# DetectLabel_Simple.net
KiCad netlist of a schematic drawn in EAGLE
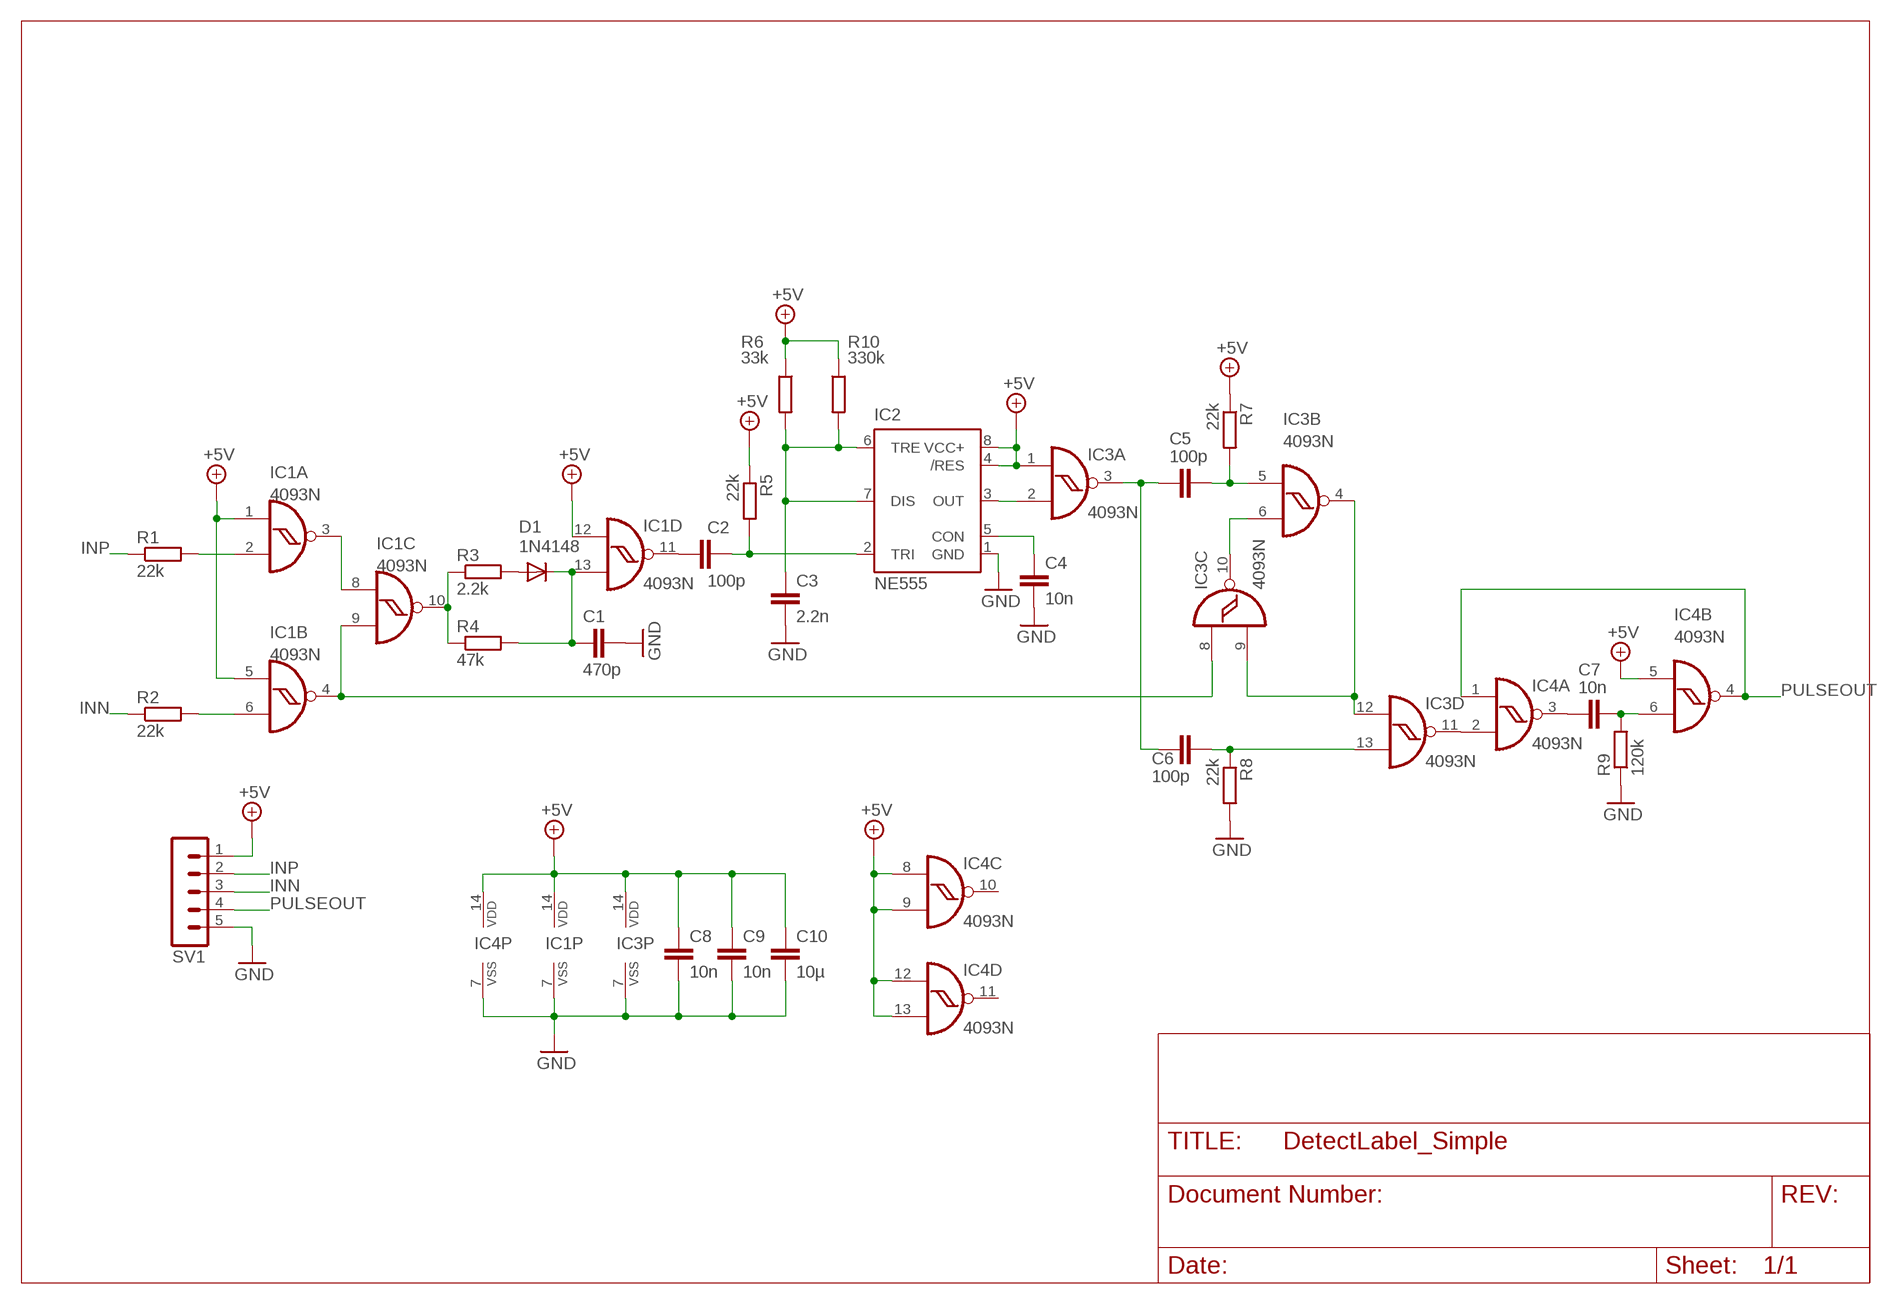
[diagram p0: schematic, sheet 1]

(export (version "E")
  (design (tool "Eeschema 10.0.6"))
  (components
    (comp (ref "C1")
      (value "470p")
      (footprint "eagle-import:C050-025X075")
      (libsource (lib "eagle-import") (part "C-EU050-025X075"))
    )
    (comp (ref "C2")
      (value "100p")
      (footprint "eagle-import:C050-025X075")
      (libsource (lib "eagle-import") (part "C-EU050-025X075"))
    )
    (comp (ref "C3")
      (value "2.2n")
      (footprint "eagle-import:C050-025X075")
      (libsource (lib "eagle-import") (part "C-EU050-025X075"))
    )
    (comp (ref "C4")
      (value "10n")
      (footprint "eagle-import:C050-025X075")
      (libsource (lib "eagle-import") (part "C-EU050-025X075"))
    )
    (comp (ref "C5")
      (value "100p")
      (footprint "eagle-import:C050-025X075")
      (libsource (lib "eagle-import") (part "C-EU050-025X075"))
    )
    (comp (ref "C6")
      (value "100p")
      (footprint "eagle-import:C050-025X075")
      (libsource (lib "eagle-import") (part "C-EU050-025X075"))
    )
    (comp (ref "C7")
      (value "10n")
      (footprint "eagle-import:C050-025X075")
      (libsource (lib "eagle-import") (part "C-EU050-025X075"))
    )
    (comp (ref "C8")
      (value "10n")
      (footprint "eagle-import:C050-025X075")
      (libsource (lib "eagle-import") (part "C-EU050-025X075"))
    )
    (comp (ref "C9")
      (value "10n")
      (footprint "eagle-import:C050-025X075")
      (libsource (lib "eagle-import") (part "C-EU050-025X075"))
    )
    (comp (ref "C10")
      (value "10µ")
      (footprint "eagle-import:C050-025X075")
      (libsource (lib "eagle-import") (part "C-EU050-025X075"))
    )
    (comp (ref "D1")
      (value "1N4148")
      (footprint "eagle-import:DO35-7")
      (libsource (lib "eagle-import") (part "1N4148DO35-7"))
    )
    (comp (ref "IC1")
      (value "4093N")
      (footprint "eagle-import:DIL14")
      (libsource (lib "eagle-import") (part "4093N"))
    )
    (comp (ref "IC2")
      (value "NE555")
      (footprint "eagle-import:DIL-08")
      (fields (field (name "MF") "Arrow Electronics") (field (name "MPN") "NE555N"))
      (libsource (lib "eagle-import") (part "NE555"))
    )
    (comp (ref "IC3")
      (value "4093N")
      (footprint "eagle-import:DIL14")
      (libsource (lib "eagle-import") (part "4093N"))
    )
    (comp (ref "IC4")
      (value "4093N")
      (footprint "eagle-import:DIL14")
      (libsource (lib "eagle-import") (part "4093N"))
    )
    (comp (ref "R1")
      (value "22k")
      (footprint "eagle-import:0309_10")
      (libsource (lib "eagle-import") (part "R-EU_0309/10"))
    )
    (comp (ref "R2")
      (value "22k")
      (footprint "eagle-import:0309_10")
      (libsource (lib "eagle-import") (part "R-EU_0309/10"))
    )
    (comp (ref "R3")
      (value "2.2k")
      (footprint "eagle-import:0309_10")
      (libsource (lib "eagle-import") (part "R-EU_0309/10"))
    )
    (comp (ref "R4")
      (value "47k")
      (footprint "eagle-import:0309_10")
      (libsource (lib "eagle-import") (part "R-EU_0309/10"))
    )
    (comp (ref "R5")
      (value "22k")
      (footprint "eagle-import:0309_10")
      (libsource (lib "eagle-import") (part "R-EU_0309/10"))
    )
    (comp (ref "R6")
      (value "33k")
      (footprint "eagle-import:0309_10")
      (libsource (lib "eagle-import") (part "R-EU_0309/10"))
    )
    (comp (ref "R7")
      (value "22k")
      (footprint "eagle-import:0309_10")
      (libsource (lib "eagle-import") (part "R-EU_0309/10"))
    )
    (comp (ref "R8")
      (value "22k")
      (footprint "eagle-import:0309_10")
      (libsource (lib "eagle-import") (part "R-EU_0309/10"))
    )
    (comp (ref "R9")
      (value "120k")
      (footprint "eagle-import:0309_10")
      (libsource (lib "eagle-import") (part "R-EU_0309/10"))
    )
    (comp (ref "R10")
      (value "330k")
      (footprint "eagle-import:0309_10")
      (libsource (lib "eagle-import") (part "R-EU_0309/10"))
    )
    (comp (ref "SV1")
      (value "MA05-1")
      (footprint "eagle-import:MA05-1")
      (libsource (lib "eagle-import") (part "MA05-1"))
    )
  )
  (nets
    (net (code "1") (name "+5V") (class "Default")
      (node (ref "C10") (pin "1") (pinfunction "1_1") (pintype "passive"))
      (node (ref "C8") (pin "1") (pinfunction "1_1") (pintype "passive"))
      (node (ref "C9") (pin "1") (pinfunction "1_1") (pintype "passive"))
      (node (ref "IC1") (pin "1") (pinfunction "I0_1") (pintype "input"))
      (node (ref "IC1") (pin "12") (pinfunction "I0_12") (pintype "input"))
      (node (ref "IC1") (pin "14") (pinfunction "VDD_14") (pintype "power_in"))
      (node (ref "IC1") (pin "5") (pinfunction "I0_5") (pintype "input"))
      (node (ref "IC2") (pin "4") (pinfunction "/RES_4") (pintype "input"))
      (node (ref "IC2") (pin "8") (pinfunction "VCC+_8") (pintype "power_in"))
      (node (ref "IC3") (pin "1") (pinfunction "I0_1") (pintype "input"))
      (node (ref "IC3") (pin "14") (pinfunction "VDD_14") (pintype "power_in"))
      (node (ref "IC4") (pin "12") (pinfunction "I0_12") (pintype "input"))
      (node (ref "IC4") (pin "13") (pinfunction "I1_13") (pintype "input"))
      (node (ref "IC4") (pin "14") (pinfunction "VDD_14") (pintype "power_in"))
      (node (ref "IC4") (pin "5") (pinfunction "I0_5") (pintype "input"))
      (node (ref "IC4") (pin "8") (pinfunction "I0_8") (pintype "input"))
      (node (ref "IC4") (pin "9") (pinfunction "I1_9") (pintype "input"))
      (node (ref "R10") (pin "1") (pinfunction "1_1") (pintype "passive"))
      (node (ref "R5") (pin "1") (pinfunction "1_1") (pintype "passive"))
      (node (ref "R6") (pin "1") (pinfunction "1_1") (pintype "passive"))
      (node (ref "R7") (pin "1") (pinfunction "1_1") (pintype "passive"))
      (node (ref "SV1") (pin "1") (pinfunction "1_1") (pintype "passive"))
    )
    (net (code "2") (name "/INN") (class "Default")
      (node (ref "R2") (pin "1") (pinfunction "1_1") (pintype "passive"))
      (node (ref "SV1") (pin "3") (pinfunction "3_3") (pintype "passive"))
    )
    (net (code "3") (name "/INP") (class "Default")
      (node (ref "R1") (pin "1") (pinfunction "1_1") (pintype "passive"))
      (node (ref "SV1") (pin "2") (pinfunction "2_2") (pintype "passive"))
    )
    (net (code "4") (name "/PULSEOUT") (class "Default")
      (node (ref "IC4") (pin "1") (pinfunction "I0_1") (pintype "input"))
      (node (ref "IC4") (pin "4") (pinfunction "O_4") (pintype "output"))
      (node (ref "SV1") (pin "4") (pinfunction "4_4") (pintype "passive"))
    )
    (net (code "5") (name "GND") (class "Default")
      (node (ref "C1") (pin "2") (pinfunction "2_2") (pintype "passive"))
      (node (ref "C10") (pin "2") (pinfunction "2_2") (pintype "passive"))
      (node (ref "C3") (pin "2") (pinfunction "2_2") (pintype "passive"))
      (node (ref "C4") (pin "2") (pinfunction "2_2") (pintype "passive"))
      (node (ref "C8") (pin "2") (pinfunction "2_2") (pintype "passive"))
      (node (ref "C9") (pin "2") (pinfunction "2_2") (pintype "passive"))
      (node (ref "IC1") (pin "7") (pinfunction "VSS_7") (pintype "power_in"))
      (node (ref "IC2") (pin "1") (pinfunction "GND_1") (pintype "power_in"))
      (node (ref "IC3") (pin "7") (pinfunction "VSS_7") (pintype "power_in"))
      (node (ref "IC4") (pin "7") (pinfunction "VSS_7") (pintype "power_in"))
      (node (ref "R8") (pin "2") (pinfunction "2_2") (pintype "passive"))
      (node (ref "R9") (pin "1") (pinfunction "1_1") (pintype "passive"))
      (node (ref "SV1") (pin "5") (pinfunction "5_5") (pintype "passive"))
    )
    (net (code "6") (name "Net-(D1-PadA)") (class "Default")
      (node (ref "D1") (pin "A") (pinfunction "A_A") (pintype "passive"))
      (node (ref "R3") (pin "2") (pinfunction "2_2") (pintype "passive"))
    )
    (net (code "7") (name "Net-(IC1A-I1)") (class "Default")
      (node (ref "IC1") (pin "2") (pinfunction "I1_2") (pintype "input"))
      (node (ref "R1") (pin "2") (pinfunction "2_2") (pintype "passive"))
    )
    (net (code "8") (name "Net-(IC1A-O)") (class "Default")
      (node (ref "IC1") (pin "3") (pinfunction "O_3") (pintype "output"))
      (node (ref "IC1") (pin "8") (pinfunction "I0_8") (pintype "input"))
    )
    (net (code "9") (name "Net-(IC1B-I1)") (class "Default")
      (node (ref "IC1") (pin "6") (pinfunction "I1_6") (pintype "input"))
      (node (ref "R2") (pin "2") (pinfunction "2_2") (pintype "passive"))
    )
    (net (code "10") (name "Net-(IC1B-O)") (class "Default")
      (node (ref "IC1") (pin "4") (pinfunction "O_4") (pintype "output"))
      (node (ref "IC1") (pin "9") (pinfunction "I1_9") (pintype "input"))
      (node (ref "IC3") (pin "8") (pinfunction "I0_8") (pintype "input"))
    )
    (net (code "11") (name "Net-(IC1C-O)") (class "Default")
      (node (ref "IC1") (pin "10") (pinfunction "O_10") (pintype "output"))
      (node (ref "R3") (pin "1") (pinfunction "1_1") (pintype "passive"))
      (node (ref "R4") (pin "1") (pinfunction "1_1") (pintype "passive"))
    )
    (net (code "12") (name "Net-(IC1D-I1)") (class "Default")
      (node (ref "C1") (pin "1") (pinfunction "1_1") (pintype "passive"))
      (node (ref "D1") (pin "C") (pinfunction "C_C") (pintype "passive"))
      (node (ref "IC1") (pin "13") (pinfunction "I1_13") (pintype "input"))
      (node (ref "R4") (pin "2") (pinfunction "2_2") (pintype "passive"))
    )
    (net (code "13") (name "Net-(IC1D-O)") (class "Default")
      (node (ref "C2") (pin "1") (pinfunction "1_1") (pintype "passive"))
      (node (ref "IC1") (pin "11") (pinfunction "O_11") (pintype "output"))
    )
    (net (code "14") (name "Net-(IC2-CON)") (class "Default")
      (node (ref "C4") (pin "1") (pinfunction "1_1") (pintype "passive"))
      (node (ref "IC2") (pin "5") (pinfunction "CON_5") (pintype "input"))
    )
    (net (code "15") (name "Net-(IC2-DIS)") (class "Default")
      (node (ref "C3") (pin "1") (pinfunction "1_1") (pintype "passive"))
      (node (ref "IC2") (pin "6") (pinfunction "TRE_6") (pintype "input"))
      (node (ref "IC2") (pin "7") (pinfunction "DIS_7") (pintype "input"))
      (node (ref "R10") (pin "2") (pinfunction "2_2") (pintype "passive"))
      (node (ref "R6") (pin "2") (pinfunction "2_2") (pintype "passive"))
    )
    (net (code "16") (name "Net-(IC2-OUT)") (class "Default")
      (node (ref "IC2") (pin "3") (pinfunction "OUT_3") (pintype "output"))
      (node (ref "IC3") (pin "2") (pinfunction "I1_2") (pintype "input"))
    )
    (net (code "17") (name "Net-(IC2-TRI)") (class "Default")
      (node (ref "C2") (pin "2") (pinfunction "2_2") (pintype "passive"))
      (node (ref "IC2") (pin "2") (pinfunction "TRI_2") (pintype "input"))
      (node (ref "R5") (pin "2") (pinfunction "2_2") (pintype "passive"))
    )
    (net (code "18") (name "Net-(IC3A-O)") (class "Default")
      (node (ref "C5") (pin "1") (pinfunction "1_1") (pintype "passive"))
      (node (ref "C6") (pin "1") (pinfunction "1_1") (pintype "passive"))
      (node (ref "IC3") (pin "3") (pinfunction "O_3") (pintype "output"))
    )
    (net (code "19") (name "Net-(IC3B-I0)") (class "Default")
      (node (ref "C5") (pin "2") (pinfunction "2_2") (pintype "passive"))
      (node (ref "IC3") (pin "5") (pinfunction "I0_5") (pintype "input"))
      (node (ref "R7") (pin "2") (pinfunction "2_2") (pintype "passive"))
    )
    (net (code "20") (name "Net-(IC3B-I1)") (class "Default")
      (node (ref "IC3") (pin "10") (pinfunction "O_10") (pintype "output"))
      (node (ref "IC3") (pin "6") (pinfunction "I1_6") (pintype "input"))
    )
    (net (code "21") (name "Net-(IC3B-O)") (class "Default")
      (node (ref "IC3") (pin "12") (pinfunction "I0_12") (pintype "input"))
      (node (ref "IC3") (pin "4") (pinfunction "O_4") (pintype "output"))
      (node (ref "IC3") (pin "9") (pinfunction "I1_9") (pintype "input"))
    )
    (net (code "22") (name "Net-(IC3D-I1)") (class "Default")
      (node (ref "C6") (pin "2") (pinfunction "2_2") (pintype "passive"))
      (node (ref "IC3") (pin "13") (pinfunction "I1_13") (pintype "input"))
      (node (ref "R8") (pin "1") (pinfunction "1_1") (pintype "passive"))
    )
    (net (code "23") (name "Net-(IC3D-O)") (class "Default")
      (node (ref "IC3") (pin "11") (pinfunction "O_11") (pintype "output"))
      (node (ref "IC4") (pin "2") (pinfunction "I1_2") (pintype "input"))
    )
    (net (code "24") (name "Net-(IC4A-O)") (class "Default")
      (node (ref "C7") (pin "1") (pinfunction "1_1") (pintype "passive"))
      (node (ref "IC4") (pin "3") (pinfunction "O_3") (pintype "output"))
    )
    (net (code "25") (name "Net-(IC4B-I1)") (class "Default")
      (node (ref "C7") (pin "2") (pinfunction "2_2") (pintype "passive"))
      (node (ref "IC4") (pin "6") (pinfunction "I1_6") (pintype "input"))
      (node (ref "R9") (pin "2") (pinfunction "2_2") (pintype "passive"))
    )
    (net (code "26") (name "unconnected-(IC4C-O-Pad10)") (class "Default")
      (node (ref "IC4") (pin "10") (pinfunction "O_10") (pintype "output"))
    )
    (net (code "27") (name "unconnected-(IC4D-O-Pad11)") (class "Default")
      (node (ref "IC4") (pin "11") (pinfunction "O_11") (pintype "output"))
    )
  )
)
